# Interface.net
KiCad netlist of a schematic drawn in Altium Designer
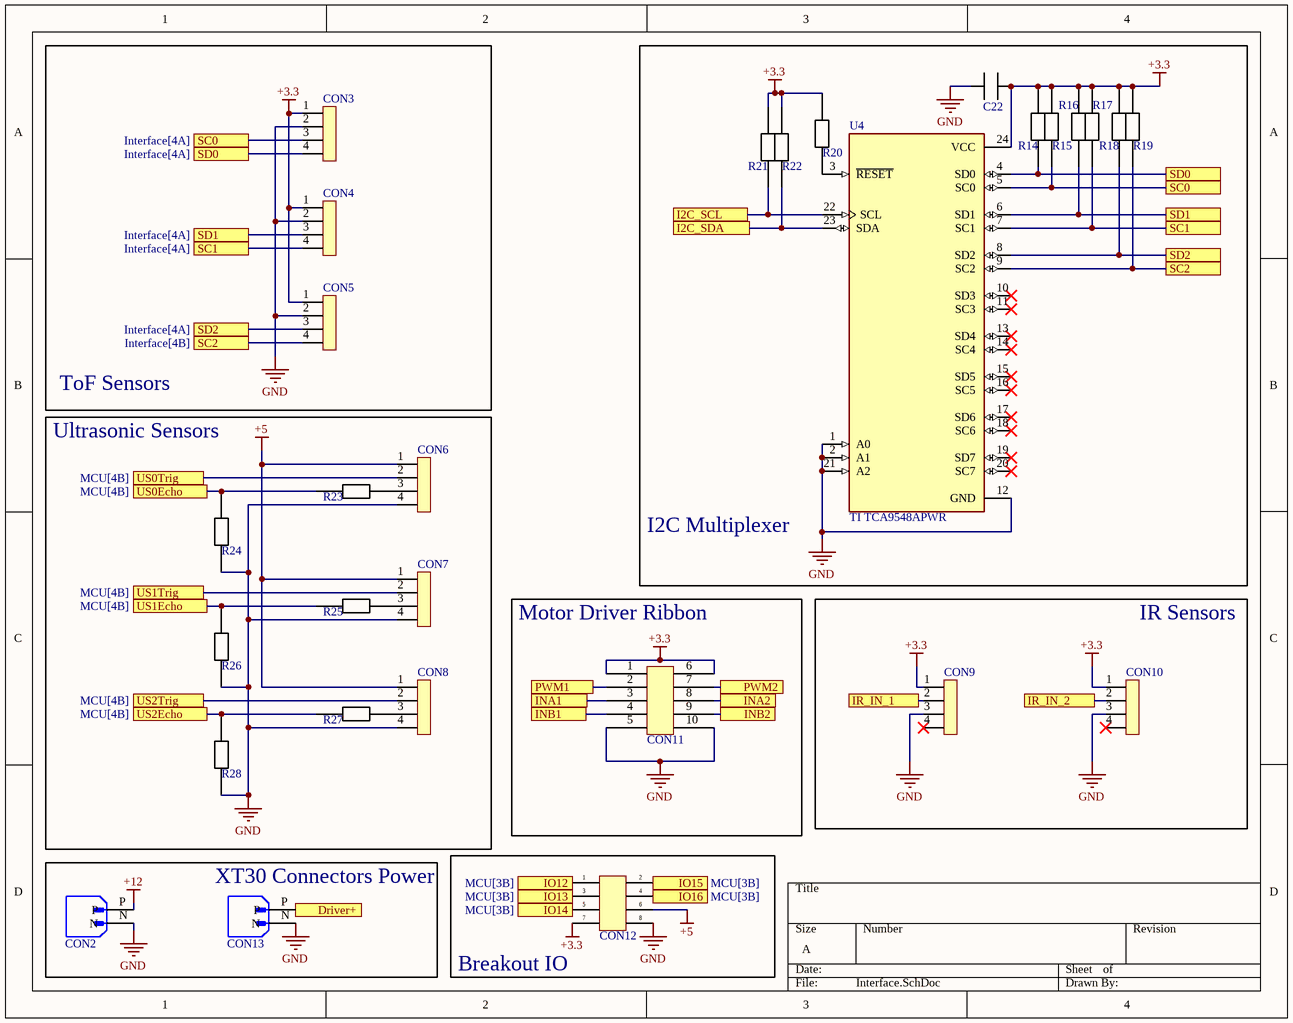
[diagram p0: Interface.SchDoc]

(export (version "E")
  (design (tool "Eeschema 10.0.6"))
  (components
    (comp (ref "C22")
      (value "100nF")
      (footprint "CAP_0805")
      (description "CAP_0805")
      (libsource (lib "Passives") (part "CAP_0805"))
    )
    (comp (ref "CON2")
      (value "Changzhou Amass Elec XT30PW-M30.G.Y")
      (footprint "XT30PW-M30.G.Y")
      (description "Banana and Tip Connector Adapters RoHS")
      (libsource (lib "Connectors") (part "XT30PW-M30.G.Y"))
    )
    (comp (ref "CON3")
      (value "HX2.54mm connector")
      (footprint "CON_1x4_HX2.54mm")
      (description "4 Pin HX2.54mm Connector Straight Needle THT")
      (libsource (lib "Connectors") (part "CON_1x4_HX2.54mm"))
    )
    (comp (ref "CON4")
      (value "HX2.54mm connector")
      (footprint "CON_1x4_HX2.54mm")
      (description "4 Pin HX2.54mm Connector Straight Needle THT")
      (libsource (lib "Connectors") (part "CON_1x4_HX2.54mm"))
    )
    (comp (ref "CON5")
      (value "HX2.54mm connector")
      (footprint "CON_1x4_HX2.54mm")
      (description "4 Pin HX2.54mm Connector Straight Needle THT")
      (libsource (lib "Connectors") (part "CON_1x4_HX2.54mm"))
    )
    (comp (ref "CON6")
      (value "HX2.54mm connector")
      (footprint "CON_1x4_HX2.54mm")
      (description "4 Pin HX2.54mm Connector Straight Needle THT")
      (libsource (lib "Connectors") (part "CON_1x4_HX2.54mm"))
    )
    (comp (ref "CON7")
      (value "HX2.54mm connector")
      (footprint "CON_1x4_HX2.54mm")
      (description "4 Pin HX2.54mm Connector Straight Needle THT")
      (libsource (lib "Connectors") (part "CON_1x4_HX2.54mm"))
    )
    (comp (ref "CON8")
      (value "HX2.54mm connector")
      (footprint "CON_1x4_HX2.54mm")
      (description "4 Pin HX2.54mm Connector Straight Needle THT")
      (libsource (lib "Connectors") (part "CON_1x4_HX2.54mm"))
    )
    (comp (ref "CON9")
      (value "HX2.54mm connector")
      (footprint "CON_1x4_HX2.54mm")
      (description "4 Pin HX2.54mm Connector Straight Needle THT")
      (libsource (lib "Connectors") (part "CON_1x4_HX2.54mm"))
    )
    (comp (ref "CON10")
      (value "HX2.54mm connector")
      (footprint "CON_1x4_HX2.54mm")
      (description "4 Pin HX2.54mm Connector Straight Needle THT")
      (libsource (lib "Connectors") (part "CON_1x4_HX2.54mm"))
    )
    (comp (ref "CON11")
      (value "BOOMELE(Boom Precision Elec) 2.54-2*5P")
      (footprint "CON_IDC_2x5_2.54")
      (description "IDC Connector 2x5 2.54mm pitch")
      (libsource (lib "Connectors") (part "CON_IDC_2x5_2.54"))
    )
    (comp (ref "CON12")
      (value "2x4 2.54mm THT")
      (footprint "CON_2x4_2.54MM_THT")
      (description "CON_2x4_2.54mm_THT")
      (libsource (lib "Connectors") (part "CON_2x4_2.54mm_THT"))
    )
    (comp (ref "CON13")
      (value "Changzhou Amass Elec XT30PW-M30.G.Y")
      (footprint "XT30PW-M30.G.Y")
      (description "Banana and Tip Connector Adapters RoHS")
      (libsource (lib "Connectors") (part "XT30PW-M30.G.Y"))
    )
    (comp (ref "R14")
      (value "5k")
      (footprint "RES_0805")
      (description "RES_0805")
      (libsource (lib "Passives") (part "RES_0805"))
    )
    (comp (ref "R15")
      (value "5k")
      (footprint "RES_0805")
      (description "RES_0805")
      (libsource (lib "Passives") (part "RES_0805"))
    )
    (comp (ref "R16")
      (value "5k")
      (footprint "RES_0805")
      (description "RES_0805")
      (libsource (lib "Passives") (part "RES_0805"))
    )
    (comp (ref "R17")
      (value "5k")
      (footprint "RES_0805")
      (description "RES_0805")
      (libsource (lib "Passives") (part "RES_0805"))
    )
    (comp (ref "R18")
      (value "5k")
      (footprint "RES_0805")
      (description "RES_0805")
      (libsource (lib "Passives") (part "RES_0805"))
    )
    (comp (ref "R19")
      (value "5k")
      (footprint "RES_0805")
      (description "RES_0805")
      (libsource (lib "Passives") (part "RES_0805"))
    )
    (comp (ref "R20")
      (value "10k")
      (footprint "RES_0805")
      (description "RES_0805")
      (libsource (lib "Passives") (part "RES_0805"))
    )
    (comp (ref "R21")
      (value "5k")
      (footprint "RES_0805")
      (description "RES_0805")
      (libsource (lib "Passives") (part "RES_0805"))
    )
    (comp (ref "R22")
      (value "5k")
      (footprint "RES_0805")
      (description "RES_0805")
      (libsource (lib "Passives") (part "RES_0805"))
    )
    (comp (ref "R23")
      (value "1k")
      (footprint "RES_0805")
      (description "RES_0805")
      (libsource (lib "Passives") (part "RES_0805"))
    )
    (comp (ref "R24")
      (value "1k")
      (footprint "RES_0805")
      (description "RES_0805")
      (libsource (lib "Passives") (part "RES_0805"))
    )
    (comp (ref "R25")
      (value "1k")
      (footprint "RES_0805")
      (description "RES_0805")
      (libsource (lib "Passives") (part "RES_0805"))
    )
    (comp (ref "R26")
      (value "1k")
      (footprint "RES_0805")
      (description "RES_0805")
      (libsource (lib "Passives") (part "RES_0805"))
    )
    (comp (ref "R27")
      (value "1k")
      (footprint "RES_0805")
      (description "RES_0805")
      (libsource (lib "Passives") (part "RES_0805"))
    )
    (comp (ref "R28")
      (value "1k")
      (footprint "RES_0805")
      (description "RES_0805")
      (libsource (lib "Passives") (part "RES_0805"))
    )
    (comp (ref "U4")
      (value "TI TCA9548APWR")
      (footprint "SOP65P640X120-24N")
      (description "1.65V~5.5V 400Kbps TSSOP-24 Signal Switches, Multiplexers, Decoders RoHS")
      (libsource (lib "IC_Digital") (part "TCA9548APWR"))
    )
  )
  (nets
    (net (code "1") (name "+3.3") (class "Default")
      (node (ref "C22") (pin "1") (pinfunction "1_1") (pintype "passive"))
      (node (ref "CON10") (pin "1") (pinfunction "1_1") (pintype "passive"))
      (node (ref "CON11") (pin "1") (pinfunction "1_1") (pintype "passive"))
      (node (ref "CON11") (pin "6") (pinfunction "6_6") (pintype "passive"))
      (node (ref "CON12") (pin "7") (pinfunction "7_7") (pintype "passive"))
      (node (ref "CON3") (pin "1") (pinfunction "1_1") (pintype "passive"))
      (node (ref "CON4") (pin "1") (pinfunction "1_1") (pintype "passive"))
      (node (ref "CON5") (pin "1") (pinfunction "1_1") (pintype "passive"))
      (node (ref "CON9") (pin "1") (pinfunction "1_1") (pintype "passive"))
      (node (ref "R14") (pin "2") (pinfunction "2_2") (pintype "passive"))
      (node (ref "R15") (pin "2") (pinfunction "2_2") (pintype "passive"))
      (node (ref "R16") (pin "2") (pinfunction "2_2") (pintype "passive"))
      (node (ref "R17") (pin "2") (pinfunction "2_2") (pintype "passive"))
      (node (ref "R18") (pin "2") (pinfunction "2_2") (pintype "passive"))
      (node (ref "R19") (pin "2") (pinfunction "2_2") (pintype "passive"))
      (node (ref "R20") (pin "2") (pinfunction "2_2") (pintype "passive"))
      (node (ref "R21") (pin "2") (pinfunction "2_2") (pintype "passive"))
      (node (ref "R22") (pin "2") (pinfunction "2_2") (pintype "passive"))
      (node (ref "U4") (pin "24") (pinfunction "VCC_24") (pintype "power_in"))
    )
    (net (code "2") (name "+5") (class "Default")
      (node (ref "CON12") (pin "6") (pinfunction "6_6") (pintype "passive"))
      (node (ref "CON6") (pin "1") (pinfunction "1_1") (pintype "passive"))
      (node (ref "CON7") (pin "1") (pinfunction "1_1") (pintype "passive"))
      (node (ref "CON8") (pin "1") (pinfunction "1_1") (pintype "passive"))
    )
    (net (code "3") (name "+12") (class "Default")
      (node (ref "CON2") (pin "P") (pinfunction "P_P") (pintype "power_in"))
    )
    (net (code "4") (name "/Driver+") (class "Default")
      (node (ref "CON13") (pin "P") (pinfunction "P_P") (pintype "power_in"))
    )
    (net (code "5") (name "/I2C_SCL") (class "Default")
      (node (ref "R21") (pin "1") (pinfunction "1_1") (pintype "passive"))
      (node (ref "U4") (pin "22") (pinfunction "SCL_22") (pintype "input"))
    )
    (net (code "6") (name "/I2C_SDA") (class "Default")
      (node (ref "R22") (pin "1") (pinfunction "1_1") (pintype "passive"))
      (node (ref "U4") (pin "23") (pinfunction "SDA_23") (pintype "bidirectional"))
    )
    (net (code "7") (name "/INA1") (class "Default")
      (node (ref "CON11") (pin "3") (pinfunction "3_3") (pintype "passive"))
    )
    (net (code "8") (name "/INA2") (class "Default")
      (node (ref "CON11") (pin "8") (pinfunction "8_8") (pintype "passive"))
    )
    (net (code "9") (name "/INB1") (class "Default")
      (node (ref "CON11") (pin "4") (pinfunction "4_4") (pintype "passive"))
    )
    (net (code "10") (name "/INB2") (class "Default")
      (node (ref "CON11") (pin "9") (pinfunction "9_9") (pintype "passive"))
    )
    (net (code "11") (name "/IO12") (class "Default")
      (node (ref "CON12") (pin "1") (pinfunction "1_1") (pintype "passive"))
    )
    (net (code "12") (name "/IO13") (class "Default")
      (node (ref "CON12") (pin "3") (pinfunction "3_3") (pintype "passive"))
    )
    (net (code "13") (name "/IO14") (class "Default")
      (node (ref "CON12") (pin "5") (pinfunction "5_5") (pintype "passive"))
    )
    (net (code "14") (name "/IO15") (class "Default")
      (node (ref "CON12") (pin "2") (pinfunction "2_2") (pintype "passive"))
    )
    (net (code "15") (name "/IO16") (class "Default")
      (node (ref "CON12") (pin "4") (pinfunction "4_4") (pintype "passive"))
    )
    (net (code "16") (name "/IR_IN_1") (class "Default")
      (node (ref "CON9") (pin "2") (pinfunction "2_2") (pintype "passive"))
    )
    (net (code "17") (name "/IR_IN_2") (class "Default")
      (node (ref "CON10") (pin "2") (pinfunction "2_2") (pintype "passive"))
    )
    (net (code "18") (name "/PWM1") (class "Default")
      (node (ref "CON11") (pin "2") (pinfunction "2_2") (pintype "passive"))
    )
    (net (code "19") (name "/PWM2") (class "Default")
      (node (ref "CON11") (pin "7") (pinfunction "7_7") (pintype "passive"))
    )
    (net (code "20") (name "/SC0") (class "Default")
      (node (ref "CON3") (pin "3") (pinfunction "3_3") (pintype "passive"))
      (node (ref "R15") (pin "1") (pinfunction "1_1") (pintype "passive"))
      (node (ref "U4") (pin "5") (pinfunction "SC0_5") (pintype "bidirectional"))
    )
    (net (code "21") (name "/SC1") (class "Default")
      (node (ref "CON4") (pin "4") (pinfunction "4_4") (pintype "passive"))
      (node (ref "R17") (pin "1") (pinfunction "1_1") (pintype "passive"))
      (node (ref "U4") (pin "7") (pinfunction "SC1_7") (pintype "bidirectional"))
    )
    (net (code "22") (name "/SC2") (class "Default")
      (node (ref "CON5") (pin "4") (pinfunction "4_4") (pintype "passive"))
      (node (ref "R19") (pin "1") (pinfunction "1_1") (pintype "passive"))
      (node (ref "U4") (pin "9") (pinfunction "SC2_9") (pintype "bidirectional"))
    )
    (net (code "23") (name "/SD0") (class "Default")
      (node (ref "CON3") (pin "4") (pinfunction "4_4") (pintype "passive"))
      (node (ref "R14") (pin "1") (pinfunction "1_1") (pintype "passive"))
      (node (ref "U4") (pin "4") (pinfunction "SD0_4") (pintype "bidirectional"))
    )
    (net (code "24") (name "/SD1") (class "Default")
      (node (ref "CON4") (pin "3") (pinfunction "3_3") (pintype "passive"))
      (node (ref "R16") (pin "1") (pinfunction "1_1") (pintype "passive"))
      (node (ref "U4") (pin "6") (pinfunction "SD1_6") (pintype "bidirectional"))
    )
    (net (code "25") (name "/SD2") (class "Default")
      (node (ref "CON5") (pin "3") (pinfunction "3_3") (pintype "passive"))
      (node (ref "R18") (pin "1") (pinfunction "1_1") (pintype "passive"))
      (node (ref "U4") (pin "8") (pinfunction "SD2_8") (pintype "bidirectional"))
    )
    (net (code "26") (name "/US0Echo") (class "Default")
      (node (ref "R23") (pin "1") (pinfunction "1_1") (pintype "passive"))
      (node (ref "R24") (pin "2") (pinfunction "2_2") (pintype "passive"))
    )
    (net (code "27") (name "/US0Trig") (class "Default")
      (node (ref "CON6") (pin "2") (pinfunction "2_2") (pintype "passive"))
    )
    (net (code "28") (name "/US1Echo") (class "Default")
      (node (ref "R25") (pin "1") (pinfunction "1_1") (pintype "passive"))
      (node (ref "R26") (pin "2") (pinfunction "2_2") (pintype "passive"))
    )
    (net (code "29") (name "/US1Trig") (class "Default")
      (node (ref "CON7") (pin "2") (pinfunction "2_2") (pintype "passive"))
    )
    (net (code "30") (name "/US2Echo") (class "Default")
      (node (ref "R27") (pin "1") (pinfunction "1_1") (pintype "passive"))
      (node (ref "R28") (pin "2") (pinfunction "2_2") (pintype "passive"))
    )
    (net (code "31") (name "/US2Trig") (class "Default")
      (node (ref "CON8") (pin "2") (pinfunction "2_2") (pintype "passive"))
    )
    (net (code "32") (name "GND") (class "Default")
      (node (ref "C22") (pin "2") (pinfunction "2_2") (pintype "passive"))
      (node (ref "CON10") (pin "3") (pinfunction "3_3") (pintype "passive"))
      (node (ref "CON11") (pin "10") (pinfunction "10_10") (pintype "passive"))
      (node (ref "CON11") (pin "5") (pinfunction "5_5") (pintype "passive"))
      (node (ref "CON12") (pin "8") (pinfunction "8_8") (pintype "passive"))
      (node (ref "CON13") (pin "N") (pinfunction "N_N") (pintype "power_in"))
      (node (ref "CON2") (pin "N") (pinfunction "N_N") (pintype "power_in"))
      (node (ref "CON3") (pin "2") (pinfunction "2_2") (pintype "passive"))
      (node (ref "CON4") (pin "2") (pinfunction "2_2") (pintype "passive"))
      (node (ref "CON5") (pin "2") (pinfunction "2_2") (pintype "passive"))
      (node (ref "CON6") (pin "4") (pinfunction "4_4") (pintype "passive"))
      (node (ref "CON7") (pin "4") (pinfunction "4_4") (pintype "passive"))
      (node (ref "CON8") (pin "4") (pinfunction "4_4") (pintype "passive"))
      (node (ref "CON9") (pin "3") (pinfunction "3_3") (pintype "passive"))
      (node (ref "R24") (pin "1") (pinfunction "1_1") (pintype "passive"))
      (node (ref "R26") (pin "1") (pinfunction "1_1") (pintype "passive"))
      (node (ref "R28") (pin "1") (pinfunction "1_1") (pintype "passive"))
      (node (ref "U4") (pin "1") (pinfunction "A0_1") (pintype "input"))
      (node (ref "U4") (pin "12") (pinfunction "GND_12") (pintype "power_in"))
      (node (ref "U4") (pin "2") (pinfunction "A1_2") (pintype "input"))
      (node (ref "U4") (pin "21") (pinfunction "A2_21") (pintype "input"))
    )
    (net (code "33") (name "Net-(CON6-Pad3)") (class "Default")
      (node (ref "CON6") (pin "3") (pinfunction "3_3") (pintype "passive"))
      (node (ref "R23") (pin "2") (pinfunction "2_2") (pintype "passive"))
    )
    (net (code "34") (name "Net-(CON7-Pad3)") (class "Default")
      (node (ref "CON7") (pin "3") (pinfunction "3_3") (pintype "passive"))
      (node (ref "R25") (pin "2") (pinfunction "2_2") (pintype "passive"))
    )
    (net (code "35") (name "Net-(CON8-Pad3)") (class "Default")
      (node (ref "CON8") (pin "3") (pinfunction "3_3") (pintype "passive"))
      (node (ref "R27") (pin "2") (pinfunction "2_2") (pintype "passive"))
    )
    (net (code "36") (name "Net-(U4-~{RESET})") (class "Default")
      (node (ref "R20") (pin "1") (pinfunction "1_1") (pintype "passive"))
      (node (ref "U4") (pin "3") (pinfunction "~{RESET}_3") (pintype "input"))
    )
    (net (code "37") (name "unconnected-(CON9-Pad4)") (class "Default")
      (node (ref "CON9") (pin "4") (pinfunction "4_4") (pintype "passive+no_connect"))
    )
    (net (code "38") (name "unconnected-(CON10-Pad4)") (class "Default")
      (node (ref "CON10") (pin "4") (pinfunction "4_4") (pintype "passive+no_connect"))
    )
    (net (code "39") (name "unconnected-(U4-SC3-Pad11)") (class "Default")
      (node (ref "U4") (pin "11") (pinfunction "SC3_11") (pintype "bidirectional+no_connect"))
    )
    (net (code "40") (name "unconnected-(U4-SC4-Pad14)") (class "Default")
      (node (ref "U4") (pin "14") (pinfunction "SC4_14") (pintype "bidirectional+no_connect"))
    )
    (net (code "41") (name "unconnected-(U4-SC5-Pad16)") (class "Default")
      (node (ref "U4") (pin "16") (pinfunction "SC5_16") (pintype "bidirectional+no_connect"))
    )
    (net (code "42") (name "unconnected-(U4-SC6-Pad18)") (class "Default")
      (node (ref "U4") (pin "18") (pinfunction "SC6_18") (pintype "bidirectional+no_connect"))
    )
    (net (code "43") (name "unconnected-(U4-SC7-Pad20)") (class "Default")
      (node (ref "U4") (pin "20") (pinfunction "SC7_20") (pintype "bidirectional+no_connect"))
    )
    (net (code "44") (name "unconnected-(U4-SD3-Pad10)") (class "Default")
      (node (ref "U4") (pin "10") (pinfunction "SD3_10") (pintype "bidirectional+no_connect"))
    )
    (net (code "45") (name "unconnected-(U4-SD4-Pad13)") (class "Default")
      (node (ref "U4") (pin "13") (pinfunction "SD4_13") (pintype "bidirectional+no_connect"))
    )
    (net (code "46") (name "unconnected-(U4-SD5-Pad15)") (class "Default")
      (node (ref "U4") (pin "15") (pinfunction "SD5_15") (pintype "bidirectional+no_connect"))
    )
    (net (code "47") (name "unconnected-(U4-SD6-Pad17)") (class "Default")
      (node (ref "U4") (pin "17") (pinfunction "SD6_17") (pintype "bidirectional+no_connect"))
    )
    (net (code "48") (name "unconnected-(U4-SD7-Pad19)") (class "Default")
      (node (ref "U4") (pin "19") (pinfunction "SD7_19") (pintype "bidirectional+no_connect"))
    )
  )
)
